# Power_Distribution_-_Turn_and_Brake_Ligh.net
KiCad netlist of a schematic drawn in Altium Designer
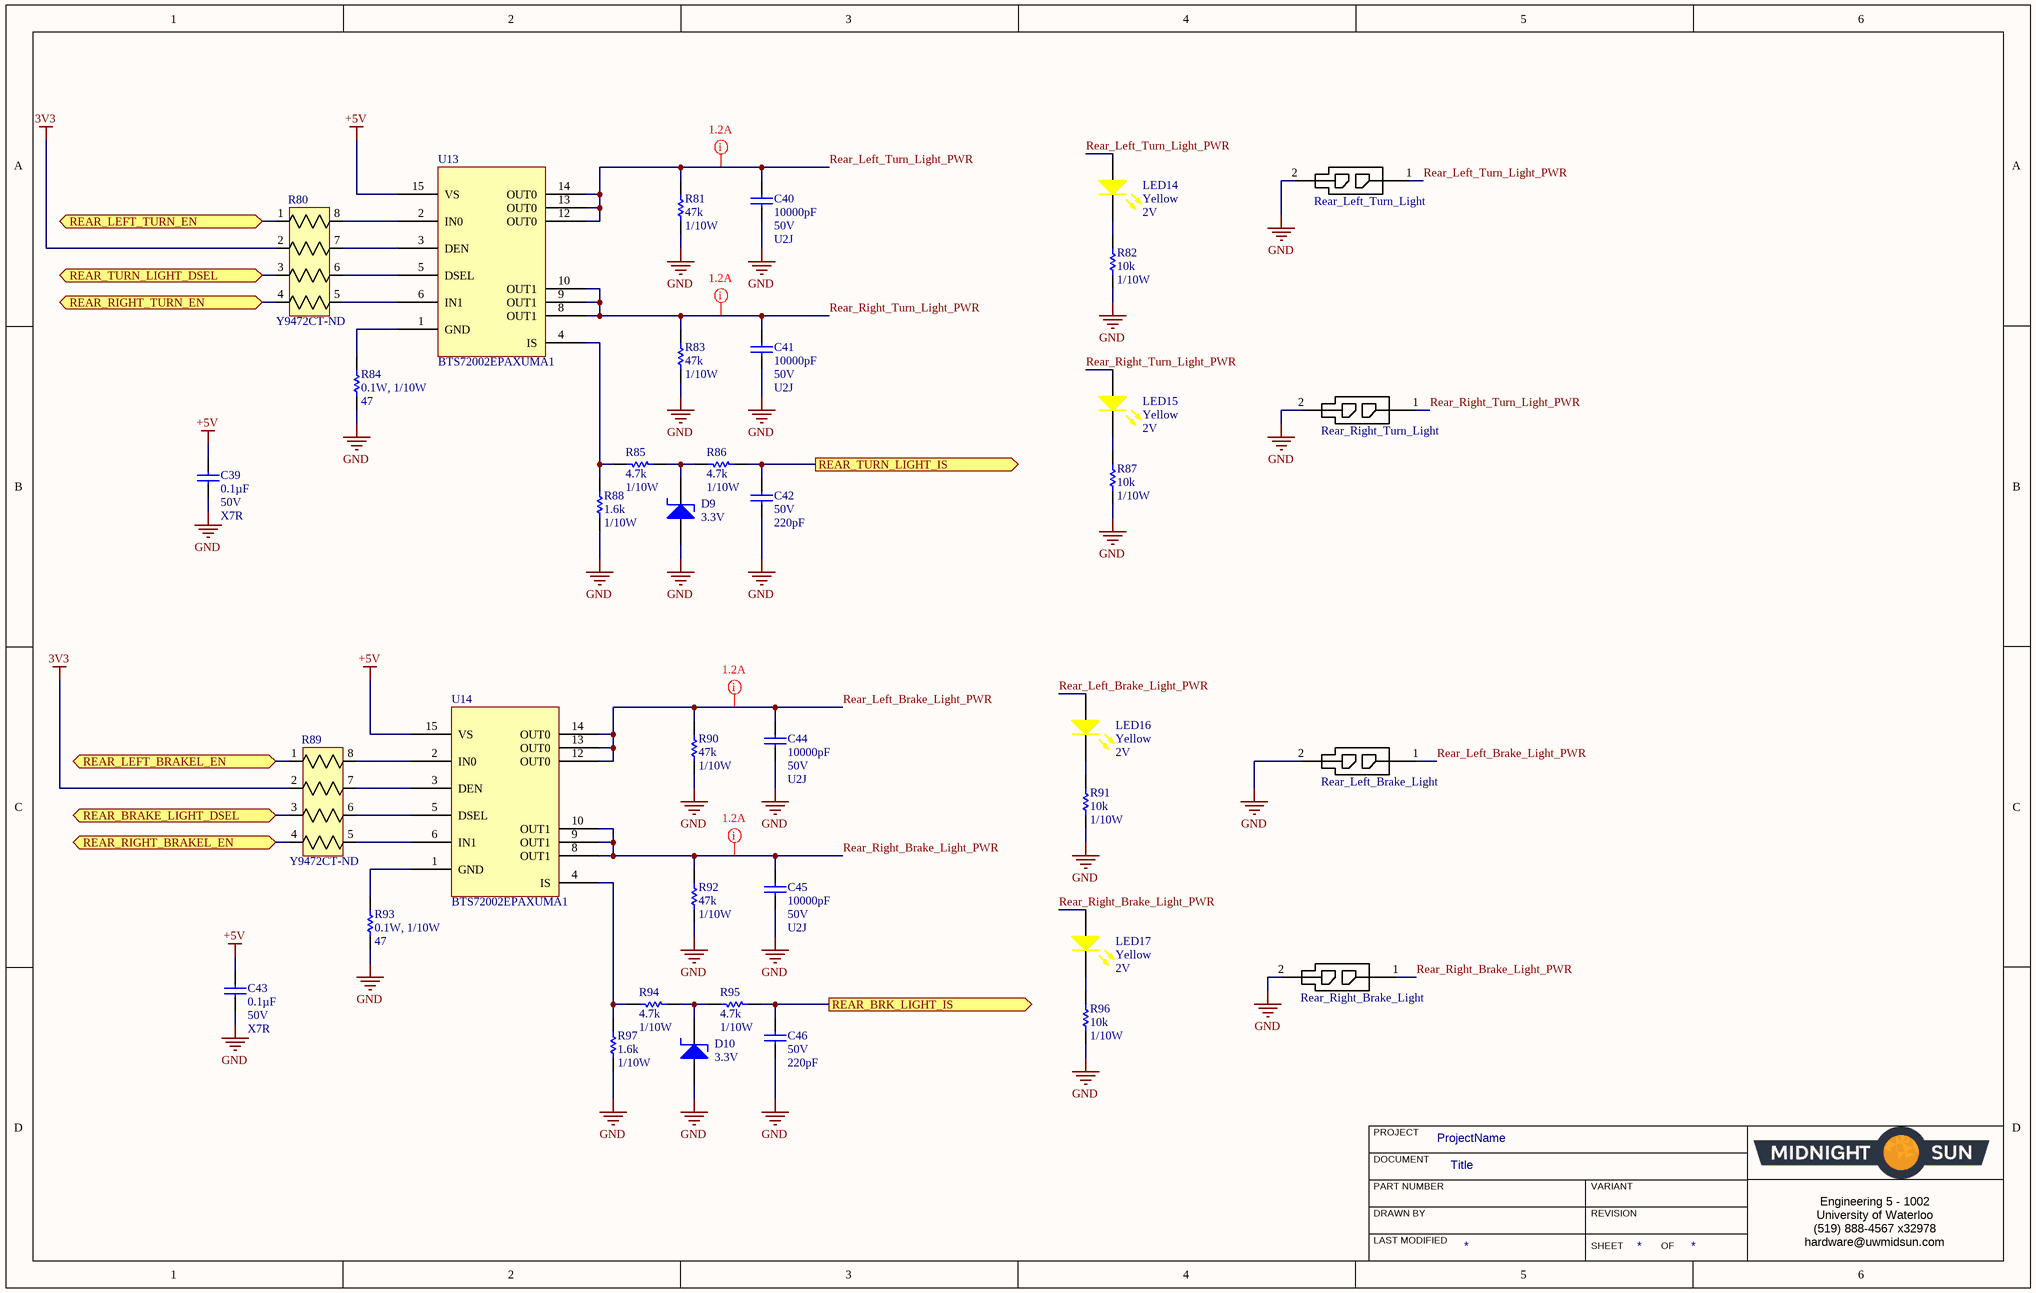
[diagram p0: Power Distribution - Turn and Brake Lights.SchDoc]

(export (version "E")
  (design (tool "Eeschema 10.0.6"))
  (components
    (comp (ref "C39")
      (value "CAP CER 0.1UF 50V 10% X7R 0603")
      (footprint "CAP, 0603")
      (description "0.10µF ±10% 50V Ceramic Capacitor X7R 0603 (1608 Metric)")
      (fields
        (field (name "TOLERANCE") "±10%")
        (field (name "CAPACITANCE") "0.1µF")
        (field (name "VOLTAGE") "50V")
        (field (name "TEMPERATURE COEFFICIENT") "X7R")
      )
      (libsource (lib "Schematic Diagrams") (part "CAP CER 0.1UF 50V 10% X7R 0603"))
    )
    (comp (ref "C40")
      (value "CAP CER 10nF 50V 5% X7R 0603")
      (footprint "CAP, 0603")
      (description "10000pF ±5% 50V Ceramic Capacitor U2J 0603 (1608 Metric)")
      (fields
        (field (name "TOLERANCE") "±5%")
        (field (name "CAPACITANCE") "10000pF")
        (field (name "VOLTAGE") "50V")
        (field (name "TEMPERATURE COEFFICIENT") "U2J")
      )
      (libsource (lib "Schematic Diagrams") (part "CAP CER 10nF 50V 5% X7R 0603"))
    )
    (comp (ref "C41")
      (value "CAP CER 10nF 50V 5% X7R 0603")
      (footprint "CAP, 0603")
      (description "10000pF ±5% 50V Ceramic Capacitor U2J 0603 (1608 Metric)")
      (fields
        (field (name "TOLERANCE") "±5%")
        (field (name "CAPACITANCE") "10000pF")
        (field (name "VOLTAGE") "50V")
        (field (name "TEMPERATURE COEFFICIENT") "U2J")
      )
      (libsource (lib "Schematic Diagrams") (part "CAP CER 10nF 50V 5% X7R 0603"))
    )
    (comp (ref "C42")
      (value "CAP CER 220PF 50V C0G/NP0 0603")
      (footprint "CAP, 0603")
      (description "220pF ±5% 50V Ceramic Capacitor C0G, NP0 0603 (1608 Metric)")
      (fields
        (field (name "MANUFACTURER") "KEMET")
        (field (name "TOLERANCE") "5%")
        (field (name "VOLTAGE RATING") "50V")
        (field (name "CAPACITANCE") "220pF")
      )
      (libsource (lib "Schematic Diagrams") (part "CAP CER 220PF 50V C0G/NP0 0603"))
    )
    (comp (ref "C43")
      (value "CAP CER 0.1UF 50V 10% X7R 0603")
      (footprint "CAP, 0603")
      (description "0.10µF ±10% 50V Ceramic Capacitor X7R 0603 (1608 Metric)")
      (fields
        (field (name "TOLERANCE") "±10%")
        (field (name "CAPACITANCE") "0.1µF")
        (field (name "VOLTAGE") "50V")
        (field (name "TEMPERATURE COEFFICIENT") "X7R")
      )
      (libsource (lib "Schematic Diagrams") (part "CAP CER 0.1UF 50V 10% X7R 0603"))
    )
    (comp (ref "C44")
      (value "CAP CER 10nF 50V 5% X7R 0603")
      (footprint "CAP, 0603")
      (description "10000pF ±5% 50V Ceramic Capacitor U2J 0603 (1608 Metric)")
      (fields
        (field (name "TOLERANCE") "±5%")
        (field (name "CAPACITANCE") "10000pF")
        (field (name "VOLTAGE") "50V")
        (field (name "TEMPERATURE COEFFICIENT") "U2J")
      )
      (libsource (lib "Schematic Diagrams") (part "CAP CER 10nF 50V 5% X7R 0603"))
    )
    (comp (ref "C45")
      (value "CAP CER 10nF 50V 5% X7R 0603")
      (footprint "CAP, 0603")
      (description "10000pF ±5% 50V Ceramic Capacitor U2J 0603 (1608 Metric)")
      (fields
        (field (name "TOLERANCE") "±5%")
        (field (name "CAPACITANCE") "10000pF")
        (field (name "VOLTAGE") "50V")
        (field (name "TEMPERATURE COEFFICIENT") "U2J")
      )
      (libsource (lib "Schematic Diagrams") (part "CAP CER 10nF 50V 5% X7R 0603"))
    )
    (comp (ref "C46")
      (value "CAP CER 220PF 50V C0G/NP0 0603")
      (footprint "CAP, 0603")
      (description "220pF ±5% 50V Ceramic Capacitor C0G, NP0 0603 (1608 Metric)")
      (fields
        (field (name "MANUFACTURER") "KEMET")
        (field (name "TOLERANCE") "5%")
        (field (name "VOLTAGE RATING") "50V")
        (field (name "CAPACITANCE") "220pF")
      )
      (libsource (lib "Schematic Diagrams") (part "CAP CER 220PF 50V C0G/NP0 0603"))
    )
    (comp (ref "D9")
      (value "DIODE ZENER 3.3V 200MW SOD323")
      (footprint "sod-323")
      (description "Zener Diode 3.3V 200mW ±5% Surface Mount SOD-323")
      (fields (field (name "VOLTAGE") "3.3V"))
      (libsource (lib "Schematic Diagrams") (part "DIODE ZENER 3.3V 200MW SOD323"))
    )
    (comp (ref "D10")
      (value "DIODE ZENER 3.3V 200MW SOD323")
      (footprint "sod-323")
      (description "Zener Diode 3.3V 200mW ±5% Surface Mount SOD-323")
      (fields (field (name "VOLTAGE") "3.3V"))
      (libsource (lib "Schematic Diagrams") (part "DIODE ZENER 3.3V 200MW SOD323"))
    )
    (comp (ref "LED14")
      (value "LED YELLOW CLEAR 2.1V 0603")
      (footprint "LED_0603")
      (description "Yellow 590nm LED Indication - Discrete 2V 0603 (1608 Metric)")
      (fields
        (field (name "MANUFACTURER") "Wurth Electronics Inc.")
        (field (name "MANUFACTURER PART NUMBER") "150060YS75000")
        (field (name "COLOR") "Yellow")
        (field (name "VOLTAGE - FORWARD (VF) (TYP)") "2V")
      )
      (libsource (lib "Schematic Diagrams") (part "LED YELLOW CLEAR 2.1V 0603"))
    )
    (comp (ref "LED15")
      (value "LED YELLOW CLEAR 2.1V 0603")
      (footprint "LED_0603")
      (description "Yellow 590nm LED Indication - Discrete 2V 0603 (1608 Metric)")
      (fields
        (field (name "MANUFACTURER") "Wurth Electronics Inc.")
        (field (name "MANUFACTURER PART NUMBER") "150060YS75000")
        (field (name "COLOR") "Yellow")
        (field (name "VOLTAGE - FORWARD (VF) (TYP)") "2V")
      )
      (libsource (lib "Schematic Diagrams") (part "LED YELLOW CLEAR 2.1V 0603"))
    )
    (comp (ref "LED16")
      (value "LED YELLOW CLEAR 2.1V 0603")
      (footprint "LED_0603")
      (description "Yellow 590nm LED Indication - Discrete 2V 0603 (1608 Metric)")
      (fields
        (field (name "MANUFACTURER") "Wurth Electronics Inc.")
        (field (name "MANUFACTURER PART NUMBER") "150060YS75000")
        (field (name "COLOR") "Yellow")
        (field (name "VOLTAGE - FORWARD (VF) (TYP)") "2V")
      )
      (libsource (lib "Schematic Diagrams") (part "LED YELLOW CLEAR 2.1V 0603"))
    )
    (comp (ref "LED17")
      (value "LED YELLOW CLEAR 2.1V 0603")
      (footprint "LED_0603")
      (description "Yellow 590nm LED Indication - Discrete 2V 0603 (1608 Metric)")
      (fields
        (field (name "MANUFACTURER") "Wurth Electronics Inc.")
        (field (name "MANUFACTURER PART NUMBER") "150060YS75000")
        (field (name "COLOR") "Yellow")
        (field (name "VOLTAGE - FORWARD (VF) (TYP)") "2V")
      )
      (libsource (lib "Schematic Diagrams") (part "LED YELLOW CLEAR 2.1V 0603"))
    )
    (comp (ref "R80")
      (value "RES ARRAY 4 RES 4.7K OHM 1206")
      (footprint "RES ARRAY 4RES 1206")
      (fields (field (name "TOLERANCE") "±5%") (field (name "SUPPLIER PART NUMBER 1") "Y9472CT-ND"))
      (libsource (lib "Schematic Diagrams") (part "RES ARRAY 4 RES 4.7K OHM 1206"))
    )
    (comp (ref "R81")
      (value "RES 47K OHM 1% 1/10W 0603")
      (footprint "RES, 0603")
      (description "47 kOhms ±1% 0.1W, 1/10W Chip Resistor 0603 (1608 Metric) Automotive AEC-Q200 Thick Film")
      (fields
        (field (name "MANUFACTURER") "Panasonic")
        (field (name "MANUFACTURER PART NUMBER") "ERJ3EKF4702V")
        (field (name "RESISTANCE") "47k")
        (field (name "POWER RATING") "1/10W")
      )
      (libsource (lib "Schematic Diagrams") (part "RES 47K OHM 1% 1/10W 0603"))
    )
    (comp (ref "R82")
      (value "RES 10K OHM 1% 1/10W 0603")
      (footprint "RES, 0603")
      (description "RES SMD 10K OHM 1% 1/10W 0603")
      (fields
        (field (name "TOLERANCE") "±1%")
        (field (name "RESISTANCE") "10k")
        (field (name "POWER") "1/10W")
      )
      (libsource (lib "Schematic Diagrams") (part "RES 10K OHM 1% 1/10W 0603"))
    )
    (comp (ref "R83")
      (value "RES 47K OHM 1% 1/10W 0603")
      (footprint "RES, 0603")
      (description "47 kOhms ±1% 0.1W, 1/10W Chip Resistor 0603 (1608 Metric) Automotive AEC-Q200 Thick Film")
      (fields
        (field (name "MANUFACTURER") "Panasonic")
        (field (name "MANUFACTURER PART NUMBER") "ERJ3EKF4702V")
        (field (name "RESISTANCE") "47k")
        (field (name "POWER RATING") "1/10W")
      )
      (libsource (lib "Schematic Diagrams") (part "RES 47K OHM 1% 1/10W 0603"))
    )
    (comp (ref "R84")
      (value "RES SMD 47 OHM 1% 1/10W 0603")
      (footprint "RES, 0603")
      (fields
        (field (name "TOLERANCE") "±1%")
        (field (name "POWER (WATTS)") "0.1W, 1/10W")
        (field (name "VALUES") "47")
      )
      (libsource (lib "Schematic Diagrams") (part "RES SMD 47 OHM 1% 1/10W 0603"))
    )
    (comp (ref "R85")
      (value "RES 4.7K OHM 1% 1/10W 0603")
      (footprint "RES, 0603")
      (description "4.7k Ohm ±1% 0.1W, 1/10W Chip Resistor 0603 (1608 Metric) Moisture Resistant Thick Film")
      (fields
        (field (name "TOLERANCE") "±1%")
        (field (name "RESISTANCE (OHMS)") "4.7k")
        (field (name "POWER (WATTS)") "1/10W")
      )
      (libsource (lib "Schematic Diagrams") (part "RES 4.7K OHM 1% 1/10W 0603"))
    )
    (comp (ref "R86")
      (value "RES 4.7K OHM 1% 1/10W 0603")
      (footprint "RES, 0603")
      (description "4.7k Ohm ±1% 0.1W, 1/10W Chip Resistor 0603 (1608 Metric) Moisture Resistant Thick Film")
      (fields
        (field (name "TOLERANCE") "±1%")
        (field (name "RESISTANCE (OHMS)") "4.7k")
        (field (name "POWER (WATTS)") "1/10W")
      )
      (libsource (lib "Schematic Diagrams") (part "RES 4.7K OHM 1% 1/10W 0603"))
    )
    (comp (ref "R87")
      (value "RES 10K OHM 1% 1/10W 0603")
      (footprint "RES, 0603")
      (description "RES SMD 10K OHM 1% 1/10W 0603")
      (fields
        (field (name "TOLERANCE") "±1%")
        (field (name "RESISTANCE") "10k")
        (field (name "POWER") "1/10W")
      )
      (libsource (lib "Schematic Diagrams") (part "RES 10K OHM 1% 1/10W 0603"))
    )
    (comp (ref "R88")
      (value "RES 1.6K OHM 1% 1/10W 0603")
      (footprint "RES, 0603")
      (description "1.6 kOhms ±1% 0.1W, 1/10W Chip Resistor 0603 (1608 Metric) Moisture Resistant Thick Film")
      (fields
        (field (name "MANUFACTURER") "Yageo")
        (field (name "MANUFACTURER PART NUMBER") "RC0603FR-071K6L")
        (field (name "RESISTANCE") "1.6k")
        (field (name "POWER RATING") "1/10W")
      )
      (libsource (lib "Schematic Diagrams") (part "RES 1.6K OHM 1% 1/10W 0603"))
    )
    (comp (ref "R89")
      (value "RES ARRAY 4 RES 4.7K OHM 1206")
      (footprint "RES ARRAY 4RES 1206")
      (fields (field (name "TOLERANCE") "±5%") (field (name "SUPPLIER PART NUMBER 1") "Y9472CT-ND"))
      (libsource (lib "Schematic Diagrams") (part "RES ARRAY 4 RES 4.7K OHM 1206"))
    )
    (comp (ref "R90")
      (value "RES 47K OHM 1% 1/10W 0603")
      (footprint "RES, 0603")
      (description "47 kOhms ±1% 0.1W, 1/10W Chip Resistor 0603 (1608 Metric) Automotive AEC-Q200 Thick Film")
      (fields
        (field (name "MANUFACTURER") "Panasonic")
        (field (name "MANUFACTURER PART NUMBER") "ERJ3EKF4702V")
        (field (name "RESISTANCE") "47k")
        (field (name "POWER RATING") "1/10W")
      )
      (libsource (lib "Schematic Diagrams") (part "RES 47K OHM 1% 1/10W 0603"))
    )
    (comp (ref "R91")
      (value "RES 10K OHM 1% 1/10W 0603")
      (footprint "RES, 0603")
      (description "RES SMD 10K OHM 1% 1/10W 0603")
      (fields
        (field (name "TOLERANCE") "±1%")
        (field (name "RESISTANCE") "10k")
        (field (name "POWER") "1/10W")
      )
      (libsource (lib "Schematic Diagrams") (part "RES 10K OHM 1% 1/10W 0603"))
    )
    (comp (ref "R92")
      (value "RES 47K OHM 1% 1/10W 0603")
      (footprint "RES, 0603")
      (description "47 kOhms ±1% 0.1W, 1/10W Chip Resistor 0603 (1608 Metric) Automotive AEC-Q200 Thick Film")
      (fields
        (field (name "MANUFACTURER") "Panasonic")
        (field (name "MANUFACTURER PART NUMBER") "ERJ3EKF4702V")
        (field (name "RESISTANCE") "47k")
        (field (name "POWER RATING") "1/10W")
      )
      (libsource (lib "Schematic Diagrams") (part "RES 47K OHM 1% 1/10W 0603"))
    )
    (comp (ref "R93")
      (value "RES SMD 47 OHM 1% 1/10W 0603")
      (footprint "RES, 0603")
      (fields
        (field (name "TOLERANCE") "±1%")
        (field (name "POWER (WATTS)") "0.1W, 1/10W")
        (field (name "VALUES") "47")
      )
      (libsource (lib "Schematic Diagrams") (part "RES SMD 47 OHM 1% 1/10W 0603"))
    )
    (comp (ref "R94")
      (value "RES 4.7K OHM 1% 1/10W 0603")
      (footprint "RES, 0603")
      (description "4.7k Ohm ±1% 0.1W, 1/10W Chip Resistor 0603 (1608 Metric) Moisture Resistant Thick Film")
      (fields
        (field (name "TOLERANCE") "±1%")
        (field (name "RESISTANCE (OHMS)") "4.7k")
        (field (name "POWER (WATTS)") "1/10W")
      )
      (libsource (lib "Schematic Diagrams") (part "RES 4.7K OHM 1% 1/10W 0603"))
    )
    (comp (ref "R95")
      (value "RES 4.7K OHM 1% 1/10W 0603")
      (footprint "RES, 0603")
      (description "4.7k Ohm ±1% 0.1W, 1/10W Chip Resistor 0603 (1608 Metric) Moisture Resistant Thick Film")
      (fields
        (field (name "TOLERANCE") "±1%")
        (field (name "RESISTANCE (OHMS)") "4.7k")
        (field (name "POWER (WATTS)") "1/10W")
      )
      (libsource (lib "Schematic Diagrams") (part "RES 4.7K OHM 1% 1/10W 0603"))
    )
    (comp (ref "R96")
      (value "RES 10K OHM 1% 1/10W 0603")
      (footprint "RES, 0603")
      (description "RES SMD 10K OHM 1% 1/10W 0603")
      (fields
        (field (name "TOLERANCE") "±1%")
        (field (name "RESISTANCE") "10k")
        (field (name "POWER") "1/10W")
      )
      (libsource (lib "Schematic Diagrams") (part "RES 10K OHM 1% 1/10W 0603"))
    )
    (comp (ref "R97")
      (value "RES 1.6K OHM 1% 1/10W 0603")
      (footprint "RES, 0603")
      (description "1.6 kOhms ±1% 0.1W, 1/10W Chip Resistor 0603 (1608 Metric) Moisture Resistant Thick Film")
      (fields
        (field (name "MANUFACTURER") "Yageo")
        (field (name "MANUFACTURER PART NUMBER") "RC0603FR-071K6L")
        (field (name "RESISTANCE") "1.6k")
        (field (name "POWER RATING") "1/10W")
      )
      (libsource (lib "Schematic Diagrams") (part "RES 1.6K OHM 1% 1/10W 0603"))
    )
    (comp (ref "Rear_Left_Brake_Light")
      (value "CONN 2POS MICRO-FIT 3mm")
      (footprint "CONN, 2POS MICRO-FIT")
      (description "Connector Header Through Hole 2 position")
      (fields (field (name "MANUFACTURER") "Molex") (field (name "MANUFACTURER PART NUMBER") "43045-0227"))
      (libsource (lib "Schematic Diagrams") (part "CONN 2POS MICRO-FIT 3mm"))
    )
    (comp (ref "Rear_Left_Turn_Light")
      (value "CONN 2POS MICRO-FIT 3mm")
      (footprint "CONN, 2POS MICRO-FIT")
      (description "Connector Header Through Hole 2 position")
      (fields (field (name "MANUFACTURER") "Molex") (field (name "MANUFACTURER PART NUMBER") "43045-0227"))
      (libsource (lib "Schematic Diagrams") (part "CONN 2POS MICRO-FIT 3mm"))
    )
    (comp (ref "Rear_Right_Brake_Light")
      (value "CONN 2POS MICRO-FIT 3mm")
      (footprint "CONN, 2POS MICRO-FIT")
      (description "Connector Header Through Hole 2 position")
      (fields (field (name "MANUFACTURER") "Molex") (field (name "MANUFACTURER PART NUMBER") "43045-0227"))
      (libsource (lib "Schematic Diagrams") (part "CONN 2POS MICRO-FIT 3mm"))
    )
    (comp (ref "Rear_Right_Turn_Light")
      (value "CONN 2POS MICRO-FIT 3mm")
      (footprint "CONN, 2POS MICRO-FIT")
      (description "Connector Header Through Hole 2 position")
      (fields (field (name "MANUFACTURER") "Molex") (field (name "MANUFACTURER PART NUMBER") "43045-0227"))
      (libsource (lib "Schematic Diagrams") (part "CONN 2POS MICRO-FIT 3mm"))
    )
    (comp (ref "U13")
      (value "IC LOAD SWITCH BTS7200-2EPA PG-TSDSO-14_1")
      (footprint "IC LOAD SWITCH PG-TSDSO-14-22")
      (description "Power Switch/Driver 1:1 N-Channel 1.2A PG-TSDSO-14-22")
      (fields
        (field (name "MANUFACTURER") "Infineon")
        (field (name "MANUFACTURER PART NUMBER") "BTS72002EPAXUMA1")
      )
      (libsource (lib "Schematic Diagrams") (part "IC LOAD SWITCH BTS7200-2EPA PG-TSDSO-14_1"))
    )
    (comp (ref "U14")
      (value "IC LOAD SWITCH BTS7200-2EPA PG-TSDSO-14_1")
      (footprint "IC LOAD SWITCH PG-TSDSO-14-22")
      (description "Power Switch/Driver 1:1 N-Channel 1.2A PG-TSDSO-14-22")
      (fields
        (field (name "MANUFACTURER") "Infineon")
        (field (name "MANUFACTURER PART NUMBER") "BTS72002EPAXUMA1")
      )
      (libsource (lib "Schematic Diagrams") (part "IC LOAD SWITCH BTS7200-2EPA PG-TSDSO-14_1"))
    )
  )
  (nets
    (net (code "1") (name "+5V") (class "Default")
      (node (ref "C39") (pin "1") (pinfunction "1_1") (pintype "passive"))
      (node (ref "C43") (pin "1") (pinfunction "1_1") (pintype "passive"))
      (node (ref "U13") (pin "15") (pinfunction "VS_15") (pintype "passive"))
      (node (ref "U14") (pin "15") (pinfunction "VS_15") (pintype "passive"))
    )
    (net (code "2") (name "/REAR_BRAKE_LIGHT_DSEL") (class "Default")
      (node (ref "R89") (pin "3") (pinfunction "3_3") (pintype "passive"))
    )
    (net (code "3") (name "/REAR_BRK_LIGHT_IS") (class "Default")
      (node (ref "C46") (pin "1") (pinfunction "1_1") (pintype "passive"))
      (node (ref "R95") (pin "1") (pinfunction "1_1") (pintype "passive"))
    )
    (net (code "4") (name "/REAR_LEFT_BRAKEL_EN") (class "Default")
      (node (ref "R89") (pin "1") (pinfunction "1_1") (pintype "passive"))
    )
    (net (code "5") (name "/REAR_LEFT_TURN_EN") (class "Default")
      (node (ref "R80") (pin "1") (pinfunction "1_1") (pintype "passive"))
    )
    (net (code "6") (name "/REAR_RIGHT_BRAKEL_EN") (class "Default")
      (node (ref "R89") (pin "4") (pinfunction "4_4") (pintype "passive"))
    )
    (net (code "7") (name "/REAR_RIGHT_TURN_EN") (class "Default")
      (node (ref "R80") (pin "4") (pinfunction "4_4") (pintype "passive"))
    )
    (net (code "8") (name "/REAR_TURN_LIGHT_DSEL") (class "Default")
      (node (ref "R80") (pin "3") (pinfunction "3_3") (pintype "passive"))
    )
    (net (code "9") (name "/REAR_TURN_LIGHT_IS") (class "Default")
      (node (ref "C42") (pin "1") (pinfunction "1_1") (pintype "passive"))
      (node (ref "R86") (pin "1") (pinfunction "1_1") (pintype "passive"))
    )
    (net (code "10") (name "/Rear_Left_Brake_Light_PWR") (class "Default")
      (node (ref "C44") (pin "1") (pinfunction "1_1") (pintype "passive"))
      (node (ref "LED16") (pin "1") (pinfunction "A_1") (pintype "passive"))
      (node (ref "R90") (pin "1") (pinfunction "1_1") (pintype "passive"))
      (node (ref "Rear_Left_Brake_Light") (pin "1") (pinfunction "1_1") (pintype "passive"))
      (node (ref "U14") (pin "12") (pinfunction "OUT0_12") (pintype "passive"))
      (node (ref "U14") (pin "13") (pinfunction "OUT0_13") (pintype "passive"))
      (node (ref "U14") (pin "14") (pinfunction "OUT0_14") (pintype "passive"))
    )
    (net (code "11") (name "/Rear_Left_Turn_Light_PWR") (class "Default")
      (node (ref "C40") (pin "1") (pinfunction "1_1") (pintype "passive"))
      (node (ref "LED14") (pin "1") (pinfunction "A_1") (pintype "passive"))
      (node (ref "R81") (pin "1") (pinfunction "1_1") (pintype "passive"))
      (node (ref "Rear_Left_Turn_Light") (pin "1") (pinfunction "1_1") (pintype "passive"))
      (node (ref "U13") (pin "12") (pinfunction "OUT0_12") (pintype "passive"))
      (node (ref "U13") (pin "13") (pinfunction "OUT0_13") (pintype "passive"))
      (node (ref "U13") (pin "14") (pinfunction "OUT0_14") (pintype "passive"))
    )
    (net (code "12") (name "/Rear_Right_Brake_Light_PWR") (class "Default")
      (node (ref "C45") (pin "1") (pinfunction "1_1") (pintype "passive"))
      (node (ref "LED17") (pin "1") (pinfunction "A_1") (pintype "passive"))
      (node (ref "R92") (pin "1") (pinfunction "1_1") (pintype "passive"))
      (node (ref "Rear_Right_Brake_Light") (pin "1") (pinfunction "1_1") (pintype "passive"))
      (node (ref "U14") (pin "10") (pinfunction "OUT1_10") (pintype "passive"))
      (node (ref "U14") (pin "8") (pinfunction "OUT1_8") (pintype "passive"))
      (node (ref "U14") (pin "9") (pinfunction "OUT1_9") (pintype "passive"))
    )
    (net (code "13") (name "/Rear_Right_Turn_Light_PWR") (class "Default")
      (node (ref "C41") (pin "1") (pinfunction "1_1") (pintype "passive"))
      (node (ref "LED15") (pin "1") (pinfunction "A_1") (pintype "passive"))
      (node (ref "R83") (pin "1") (pinfunction "1_1") (pintype "passive"))
      (node (ref "Rear_Right_Turn_Light") (pin "1") (pinfunction "1_1") (pintype "passive"))
      (node (ref "U13") (pin "10") (pinfunction "OUT1_10") (pintype "passive"))
      (node (ref "U13") (pin "8") (pinfunction "OUT1_8") (pintype "passive"))
      (node (ref "U13") (pin "9") (pinfunction "OUT1_9") (pintype "passive"))
    )
    (net (code "14") (name "3V3") (class "Default")
      (node (ref "R80") (pin "2") (pinfunction "2_2") (pintype "passive"))
      (node (ref "R89") (pin "2") (pinfunction "2_2") (pintype "passive"))
    )
    (net (code "15") (name "GND") (class "Default")
      (node (ref "C39") (pin "2") (pinfunction "2_2") (pintype "passive"))
      (node (ref "C40") (pin "2") (pinfunction "2_2") (pintype "passive"))
      (node (ref "C41") (pin "2") (pinfunction "2_2") (pintype "passive"))
      (node (ref "C42") (pin "2") (pinfunction "2_2") (pintype "passive"))
      (node (ref "C43") (pin "2") (pinfunction "2_2") (pintype "passive"))
      (node (ref "C44") (pin "2") (pinfunction "2_2") (pintype "passive"))
      (node (ref "C45") (pin "2") (pinfunction "2_2") (pintype "passive"))
      (node (ref "C46") (pin "2") (pinfunction "2_2") (pintype "passive"))
      (node (ref "D10") (pin "1") (pinfunction "A_1") (pintype "passive"))
      (node (ref "D9") (pin "1") (pinfunction "A_1") (pintype "passive"))
      (node (ref "R81") (pin "2") (pinfunction "2_2") (pintype "passive"))
      (node (ref "R82") (pin "2") (pinfunction "2_2") (pintype "passive"))
      (node (ref "R83") (pin "2") (pinfunction "2_2") (pintype "passive"))
      (node (ref "R84") (pin "2") (pinfunction "2_2") (pintype "passive"))
      (node (ref "R87") (pin "2") (pinfunction "2_2") (pintype "passive"))
      (node (ref "R88") (pin "2") (pinfunction "2_2") (pintype "passive"))
      (node (ref "R90") (pin "2") (pinfunction "2_2") (pintype "passive"))
      (node (ref "R91") (pin "2") (pinfunction "2_2") (pintype "passive"))
      (node (ref "R92") (pin "2") (pinfunction "2_2") (pintype "passive"))
      (node (ref "R93") (pin "2") (pinfunction "2_2") (pintype "passive"))
      (node (ref "R96") (pin "2") (pinfunction "2_2") (pintype "passive"))
      (node (ref "R97") (pin "2") (pinfunction "2_2") (pintype "passive"))
      (node (ref "Rear_Left_Brake_Light") (pin "2") (pinfunction "2_2") (pintype "passive"))
      (node (ref "Rear_Left_Turn_Light") (pin "2") (pinfunction "2_2") (pintype "passive"))
      (node (ref "Rear_Right_Brake_Light") (pin "2") (pinfunction "2_2") (pintype "passive"))
      (node (ref "Rear_Right_Turn_Light") (pin "2") (pinfunction "2_2") (pintype "passive"))
    )
    (net (code "16") (name "Net-(D9-K)") (class "Default")
      (node (ref "D9") (pin "2") (pinfunction "K_2") (pintype "passive"))
      (node (ref "R85") (pin "1") (pinfunction "1_1") (pintype "passive"))
      (node (ref "R86") (pin "2") (pinfunction "2_2") (pintype "passive"))
    )
    (net (code "17") (name "Net-(D10-K)") (class "Default")
      (node (ref "D10") (pin "2") (pinfunction "K_2") (pintype "passive"))
      (node (ref "R94") (pin "1") (pinfunction "1_1") (pintype "passive"))
      (node (ref "R95") (pin "2") (pinfunction "2_2") (pintype "passive"))
    )
    (net (code "18") (name "Net-(LED14-K)") (class "Default")
      (node (ref "LED14") (pin "2") (pinfunction "K_2") (pintype "passive"))
      (node (ref "R82") (pin "1") (pinfunction "1_1") (pintype "passive"))
    )
    (net (code "19") (name "Net-(LED15-K)") (class "Default")
      (node (ref "LED15") (pin "2") (pinfunction "K_2") (pintype "passive"))
      (node (ref "R87") (pin "1") (pinfunction "1_1") (pintype "passive"))
    )
    (net (code "20") (name "Net-(LED16-K)") (class "Default")
      (node (ref "LED16") (pin "2") (pinfunction "K_2") (pintype "passive"))
      (node (ref "R91") (pin "1") (pinfunction "1_1") (pintype "passive"))
    )
    (net (code "21") (name "Net-(LED17-K)") (class "Default")
      (node (ref "LED17") (pin "2") (pinfunction "K_2") (pintype "passive"))
      (node (ref "R96") (pin "1") (pinfunction "1_1") (pintype "passive"))
    )
    (net (code "22") (name "Net-(U13-DEN)") (class "Default")
      (node (ref "R80") (pin "7") (pinfunction "7_7") (pintype "passive"))
      (node (ref "U13") (pin "3") (pinfunction "DEN_3") (pintype "passive"))
    )
    (net (code "23") (name "Net-(U13-DSEL)") (class "Default")
      (node (ref "R80") (pin "6") (pinfunction "6_6") (pintype "passive"))
      (node (ref "U13") (pin "5") (pinfunction "DSEL_5") (pintype "passive"))
    )
    (net (code "24") (name "Net-(U13-GND)") (class "Default")
      (node (ref "R84") (pin "1") (pinfunction "1_1") (pintype "passive"))
      (node (ref "U13") (pin "1") (pinfunction "GND_1") (pintype "passive"))
    )
    (net (code "25") (name "Net-(U13-IN0)") (class "Default")
      (node (ref "R80") (pin "8") (pinfunction "8_8") (pintype "passive"))
      (node (ref "U13") (pin "2") (pinfunction "IN0_2") (pintype "passive"))
    )
    (net (code "26") (name "Net-(U13-IN1)") (class "Default")
      (node (ref "R80") (pin "5") (pinfunction "5_5") (pintype "passive"))
      (node (ref "U13") (pin "6") (pinfunction "IN1_6") (pintype "passive"))
    )
    (net (code "27") (name "Net-(U13-IS)") (class "Default")
      (node (ref "R85") (pin "2") (pinfunction "2_2") (pintype "passive"))
      (node (ref "R88") (pin "1") (pinfunction "1_1") (pintype "passive"))
      (node (ref "U13") (pin "4") (pinfunction "IS_4") (pintype "passive"))
    )
    (net (code "28") (name "Net-(U14-DEN)") (class "Default")
      (node (ref "R89") (pin "7") (pinfunction "7_7") (pintype "passive"))
      (node (ref "U14") (pin "3") (pinfunction "DEN_3") (pintype "passive"))
    )
    (net (code "29") (name "Net-(U14-DSEL)") (class "Default")
      (node (ref "R89") (pin "6") (pinfunction "6_6") (pintype "passive"))
      (node (ref "U14") (pin "5") (pinfunction "DSEL_5") (pintype "passive"))
    )
    (net (code "30") (name "Net-(U14-GND)") (class "Default")
      (node (ref "R93") (pin "1") (pinfunction "1_1") (pintype "passive"))
      (node (ref "U14") (pin "1") (pinfunction "GND_1") (pintype "passive"))
    )
    (net (code "31") (name "Net-(U14-IN0)") (class "Default")
      (node (ref "R89") (pin "8") (pinfunction "8_8") (pintype "passive"))
      (node (ref "U14") (pin "2") (pinfunction "IN0_2") (pintype "passive"))
    )
    (net (code "32") (name "Net-(U14-IN1)") (class "Default")
      (node (ref "R89") (pin "5") (pinfunction "5_5") (pintype "passive"))
      (node (ref "U14") (pin "6") (pinfunction "IN1_6") (pintype "passive"))
    )
    (net (code "33") (name "Net-(U14-IS)") (class "Default")
      (node (ref "R94") (pin "2") (pinfunction "2_2") (pintype "passive"))
      (node (ref "R97") (pin "1") (pinfunction "1_1") (pintype "passive"))
      (node (ref "U14") (pin "4") (pinfunction "IS_4") (pintype "passive"))
    )
  )
)
